# MacroQMK.net
KiCad netlist of a schematic drawn in Altium Designer
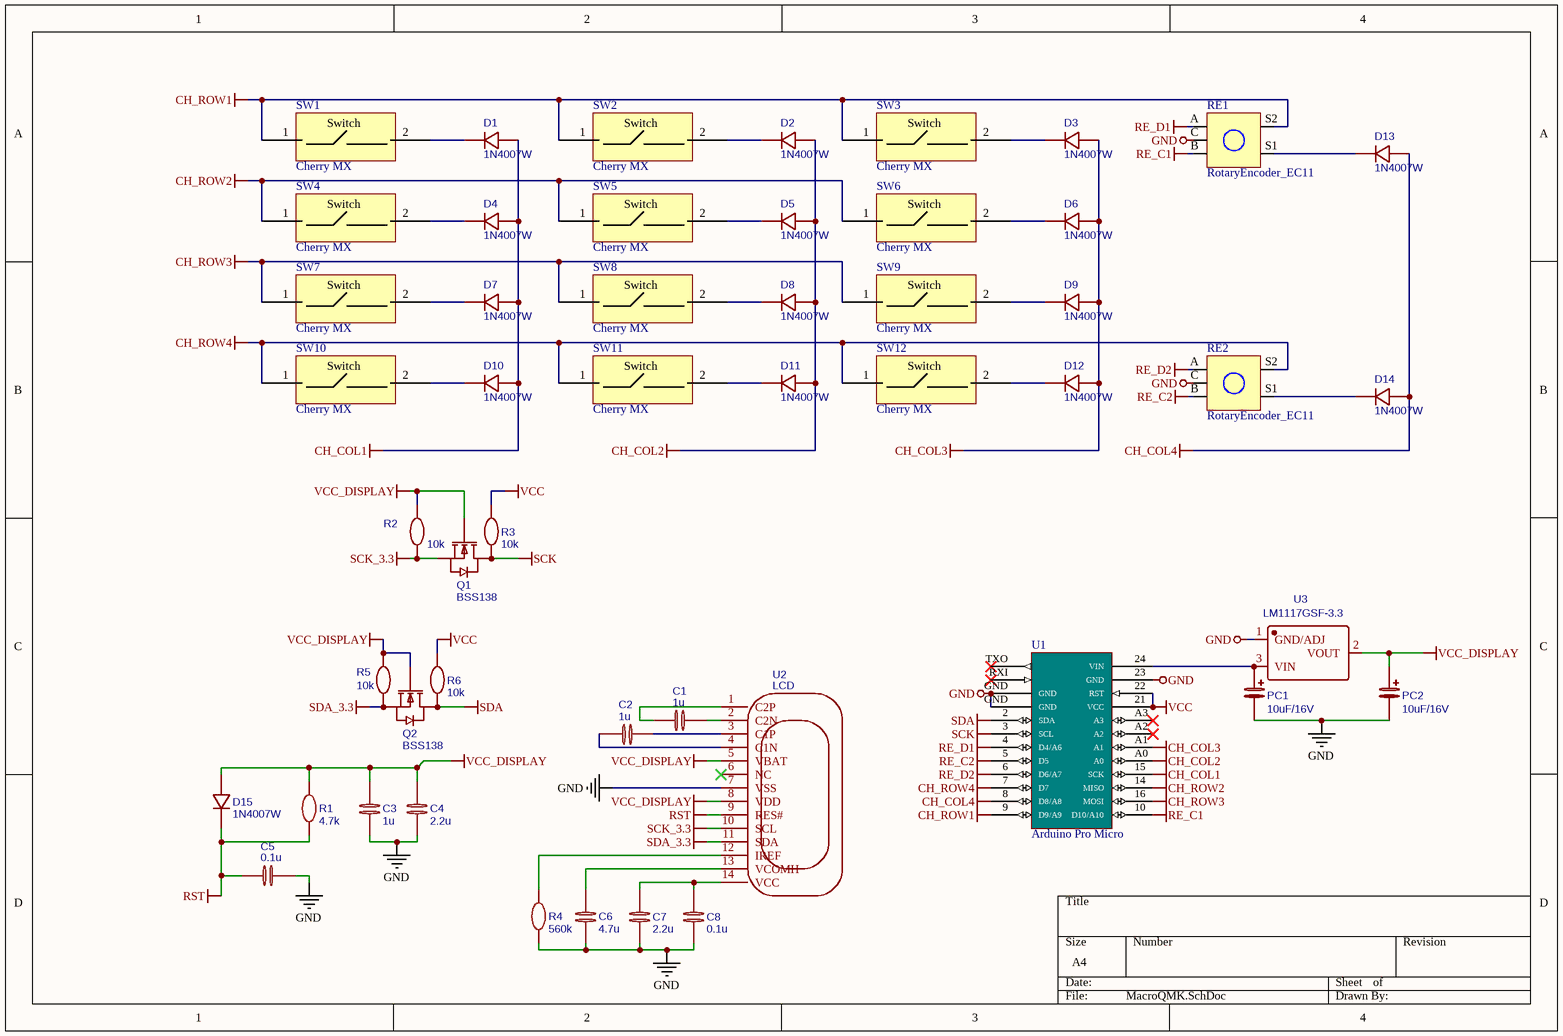
[diagram p0: MacroQMK.SchDoc]

(export (version "E")
  (design (tool "Eeschema 10.0.6"))
  (components
    (comp (ref "C1")
      (value "1u")
      (footprint "C0603")
      (fields (field (name "CONTRIBUTOR") "LCEDA_Lib"))
      (libsource (lib "altium-import") (part "root_0_1u_"))
    )
    (comp (ref "C2")
      (value "1u")
      (footprint "C0603")
      (fields (field (name "CONTRIBUTOR") "LCEDA_Lib"))
      (libsource (lib "altium-import") (part "root_2_1u_"))
    )
    (comp (ref "C3")
      (value "1u")
      (footprint "C0603")
      (fields (field (name "CONTRIBUTOR") "LCEDA_Lib"))
      (libsource (lib "altium-import") (part "root_1_1u_"))
    )
    (comp (ref "C4")
      (value "2.2u")
      (footprint "C0603")
      (fields (field (name "CONTRIBUTOR") "LCEDA_Lib"))
      (libsource (lib "altium-import") (part "root_1_2.2u_"))
    )
    (comp (ref "C5")
      (value "0.1u")
      (footprint "C0603")
      (fields (field (name "CONTRIBUTOR") "LCEDA_Lib"))
      (libsource (lib "altium-import") (part "root_0_0.1u_"))
    )
    (comp (ref "C6")
      (value "4.7u")
      (footprint "C0603")
      (fields (field (name "CONTRIBUTOR") "LCEDA_Lib"))
      (libsource (lib "altium-import") (part "root_1_4.7u_"))
    )
    (comp (ref "C7")
      (value "2.2u")
      (footprint "C0603")
      (fields (field (name "CONTRIBUTOR") "LCEDA_Lib"))
      (libsource (lib "altium-import") (part "root_1_2.2u_"))
    )
    (comp (ref "C8")
      (value "0.1u")
      (footprint "C0603")
      (fields (field (name "CONTRIBUTOR") "LCEDA_Lib"))
      (libsource (lib "altium-import") (part "root_1_0.1u_"))
    )
    (comp (ref "D1")
      (value "1N4007W")
      (footprint "SOD123F")
      (fields (field (name "BOM_SUPPLIER PART") "C328592") (field (name "CONTRIBUTOR") "LCEDA_Lib"))
      (libsource (lib "altium-import") (part "root_2_1N4007W_"))
    )
    (comp (ref "D2")
      (value "1N4007W")
      (footprint "SOD123F")
      (fields (field (name "BOM_SUPPLIER PART") "C328592") (field (name "CONTRIBUTOR") "LCEDA_Lib"))
      (libsource (lib "altium-import") (part "root_2_1N4007W_"))
    )
    (comp (ref "D3")
      (value "1N4007W")
      (footprint "SOD123F")
      (fields (field (name "BOM_SUPPLIER PART") "C328592") (field (name "CONTRIBUTOR") "LCEDA_Lib"))
      (libsource (lib "altium-import") (part "root_2_1N4007W_"))
    )
    (comp (ref "D4")
      (value "1N4007W")
      (footprint "SOD123F")
      (fields (field (name "BOM_SUPPLIER PART") "C328592") (field (name "CONTRIBUTOR") "LCEDA_Lib"))
      (libsource (lib "altium-import") (part "root_2_1N4007W_"))
    )
    (comp (ref "D5")
      (value "1N4007W")
      (footprint "SOD123F")
      (fields (field (name "BOM_SUPPLIER PART") "C328592") (field (name "CONTRIBUTOR") "LCEDA_Lib"))
      (libsource (lib "altium-import") (part "root_2_1N4007W_"))
    )
    (comp (ref "D6")
      (value "1N4007W")
      (footprint "SOD123F")
      (fields (field (name "BOM_SUPPLIER PART") "C328592") (field (name "CONTRIBUTOR") "LCEDA_Lib"))
      (libsource (lib "altium-import") (part "root_2_1N4007W_"))
    )
    (comp (ref "D7")
      (value "1N4007W")
      (footprint "SOD123F")
      (fields (field (name "BOM_SUPPLIER PART") "C328592") (field (name "CONTRIBUTOR") "LCEDA_Lib"))
      (libsource (lib "altium-import") (part "root_2_1N4007W_"))
    )
    (comp (ref "D8")
      (value "1N4007W")
      (footprint "SOD123F")
      (fields (field (name "BOM_SUPPLIER PART") "C328592") (field (name "CONTRIBUTOR") "LCEDA_Lib"))
      (libsource (lib "altium-import") (part "root_2_1N4007W_"))
    )
    (comp (ref "D9")
      (value "1N4007W")
      (footprint "SOD123F")
      (fields (field (name "BOM_SUPPLIER PART") "C328592") (field (name "CONTRIBUTOR") "LCEDA_Lib"))
      (libsource (lib "altium-import") (part "root_2_1N4007W_"))
    )
    (comp (ref "D10")
      (value "1N4007W")
      (footprint "SOD123F")
      (fields (field (name "BOM_SUPPLIER PART") "C328592") (field (name "CONTRIBUTOR") "LCEDA_Lib"))
      (libsource (lib "altium-import") (part "root_2_1N4007W_"))
    )
    (comp (ref "D11")
      (value "1N4007W")
      (footprint "SOD123F")
      (fields (field (name "BOM_SUPPLIER PART") "C328592") (field (name "CONTRIBUTOR") "LCEDA_Lib"))
      (libsource (lib "altium-import") (part "root_2_1N4007W_"))
    )
    (comp (ref "D12")
      (value "1N4007W")
      (footprint "SOD123F")
      (fields (field (name "BOM_SUPPLIER PART") "C328592") (field (name "CONTRIBUTOR") "LCEDA_Lib"))
      (libsource (lib "altium-import") (part "root_2_1N4007W_"))
    )
    (comp (ref "D13")
      (value "1N4007W")
      (footprint "SOD123F")
      (fields (field (name "BOM_SUPPLIER PART") "C328592") (field (name "CONTRIBUTOR") "LCEDA_Lib"))
      (libsource (lib "altium-import") (part "root_2_1N4007W_"))
    )
    (comp (ref "D14")
      (value "1N4007W")
      (footprint "SOD123F")
      (fields (field (name "BOM_SUPPLIER PART") "C328592") (field (name "CONTRIBUTOR") "LCEDA_Lib"))
      (libsource (lib "altium-import") (part "root_2_1N4007W_"))
    )
    (comp (ref "D15")
      (value "1N4007W")
      (footprint "SOD123F")
      (fields (field (name "BOM_SUPPLIER PART") "C328592") (field (name "CONTRIBUTOR") "LCEDA_Lib"))
      (libsource (lib "altium-import") (part "root_3_1N4007W_"))
    )
    (comp (ref "PC1")
      (value "10uF/16V")
      (footprint "CAP POL 1206_3216")
      (fields (field (name "BOM_MANUFACTURER PART") "?"))
      (libsource (lib "altium-import") (part "root_0_10uF/16V_"))
    )
    (comp (ref "PC2")
      (value "10uF/16V")
      (footprint "CAP POL 1206_3216")
      (fields (field (name "BOM_MANUFACTURER PART") "?"))
      (libsource (lib "altium-import") (part "root_0_10uF/16V_"))
    )
    (comp (ref "Q1")
      (value "BSS138")
      (footprint "MICROCHIP SOT-23-3 NB")
      (fields (field (name "BOM_MANUFACTURER PART") "BSS138LT1G") (field (name "BOM_SUPPLIER PART") "C82045"))
      (libsource (lib "altium-import") (part "root_3_BSS138_"))
    )
    (comp (ref "Q2")
      (value "BSS138")
      (footprint "MICROCHIP SOT-23-3 NB")
      (fields (field (name "BOM_MANUFACTURER PART") "BSS138LT1G") (field (name "BOM_SUPPLIER PART") "C82045"))
      (libsource (lib "altium-import") (part "root_3_BSS138_"))
    )
    (comp (ref "R1")
      (value "4.7k")
      (footprint "RES 0402_1005")
      (fields (field (name "CONTRIBUTOR") "LCEDA_Lib"))
      (libsource (lib "altium-import") (part "root_1_4.7k_"))
    )
    (comp (ref "R2")
      (value "10k")
      (footprint "R0603")
      (fields (field (name "CONTRIBUTOR") "LCEDA_Lib"))
      (libsource (lib "altium-import") (part "root_3_10k_"))
    )
    (comp (ref "R3")
      (value "10k")
      (footprint "R0603")
      (fields (field (name "CONTRIBUTOR") "LCEDA_Lib"))
      (libsource (lib "altium-import") (part "root_3_10k_"))
    )
    (comp (ref "R4")
      (value "560k")
      (footprint "R0603")
      (fields (field (name "CONTRIBUTOR") "LCEDA_Lib"))
      (libsource (lib "altium-import") (part "root_1_560k_"))
    )
    (comp (ref "R5")
      (value "10k")
      (footprint "R0603")
      (fields (field (name "CONTRIBUTOR") "LCEDA_Lib"))
      (libsource (lib "altium-import") (part "root_3_10k_"))
    )
    (comp (ref "R6")
      (value "10k")
      (footprint "R0603")
      (fields (field (name "CONTRIBUTOR") "LCEDA_Lib"))
      (libsource (lib "altium-import") (part "root_3_10k_"))
    )
    (comp (ref "RE1")
      (value "RotaryEncoder_EC11")
      (footprint "RotaryEncoder_EC11")
      (libsource (lib "MacroQMK") (part "RotaryEncoder_EC11"))
    )
    (comp (ref "RE2")
      (value "RotaryEncoder_EC11")
      (footprint "RotaryEncoder_EC11")
      (libsource (lib "MacroQMK") (part "RotaryEncoder_EC11"))
    )
    (comp (ref "SW1")
      (value "Cherry MX")
      (footprint "MX_Cherry")
      (libsource (lib "MacroQMK") (part "MX_Cherry"))
    )
    (comp (ref "SW2")
      (value "Cherry MX")
      (footprint "MX_Cherry")
      (libsource (lib "MacroQMK") (part "MX_Cherry"))
    )
    (comp (ref "SW3")
      (value "Cherry MX")
      (footprint "MX_Cherry")
      (libsource (lib "MacroQMK") (part "MX_Cherry"))
    )
    (comp (ref "SW4")
      (value "Cherry MX")
      (footprint "MX_Cherry")
      (libsource (lib "MacroQMK") (part "MX_Cherry"))
    )
    (comp (ref "SW5")
      (value "Cherry MX")
      (footprint "MX_Cherry")
      (libsource (lib "MacroQMK") (part "MX_Cherry"))
    )
    (comp (ref "SW6")
      (value "Cherry MX")
      (footprint "MX_Cherry")
      (libsource (lib "MacroQMK") (part "MX_Cherry"))
    )
    (comp (ref "SW7")
      (value "Cherry MX")
      (footprint "MX_Cherry")
      (libsource (lib "MacroQMK") (part "MX_Cherry"))
    )
    (comp (ref "SW8")
      (value "Cherry MX")
      (footprint "MX_Cherry")
      (libsource (lib "MacroQMK") (part "MX_Cherry"))
    )
    (comp (ref "SW9")
      (value "Cherry MX")
      (footprint "MX_Cherry")
      (libsource (lib "MacroQMK") (part "MX_Cherry"))
    )
    (comp (ref "SW10")
      (value "Cherry MX")
      (footprint "MX_Cherry")
      (libsource (lib "MacroQMK") (part "MX_Cherry"))
    )
    (comp (ref "SW11")
      (value "Cherry MX")
      (footprint "MX_Cherry")
      (libsource (lib "MacroQMK") (part "MX_Cherry"))
    )
    (comp (ref "SW12")
      (value "Cherry MX")
      (footprint "MX_Cherry")
      (libsource (lib "MacroQMK") (part "MX_Cherry"))
    )
    (comp (ref "U1")
      (value "Arduino Pro Micro")
      (footprint "ArduinoProMicro")
      (libsource (lib "MacroQMK") (part "ArduinoProMicro"))
    )
    (comp (ref "U2")
      (value "LCD")
      (footprint "GCT FFC2B28-14")
      (fields (field (name "CONTRIBUTOR") "Jose Manuel Ordo?ez Gongora"))
      (libsource (lib "altium-import") (part "root_3_LCD_"))
    )
    (comp (ref "U3")
      (value "LM1117GSF-3.3")
      (footprint "NEXPERIA SOT-223 BZV90")
      (fields (field (name "BOM_SUPPLIER PART") "C481677") (field (name "CONTRIBUTOR") "LCSC"))
      (libsource (lib "altium-import") (part "root_0_LM1117GSF-3.3_"))
    )
  )
  (nets
    (net (code "1") (name "CH_COL1") (class "Default")
      (node (ref "D1") (pin "2") (pinfunction "2_2") (pintype "passive"))
      (node (ref "D10") (pin "2") (pinfunction "2_2") (pintype "passive"))
      (node (ref "D4") (pin "2") (pinfunction "2_2") (pintype "passive"))
      (node (ref "D7") (pin "2") (pinfunction "2_2") (pintype "passive"))
      (node (ref "U1") (pin "15") (pinfunction "SCK_15") (pintype "bidirectional"))
    )
    (net (code "2") (name "CH_COL2") (class "Default")
      (node (ref "D11") (pin "2") (pinfunction "2_2") (pintype "passive"))
      (node (ref "D2") (pin "2") (pinfunction "2_2") (pintype "passive"))
      (node (ref "D5") (pin "2") (pinfunction "2_2") (pintype "passive"))
      (node (ref "D8") (pin "2") (pinfunction "2_2") (pintype "passive"))
      (node (ref "U1") (pin "A0") (pinfunction "A0_A0") (pintype "bidirectional"))
    )
    (net (code "3") (name "CH_COL3") (class "Default")
      (node (ref "D12") (pin "2") (pinfunction "2_2") (pintype "passive"))
      (node (ref "D3") (pin "2") (pinfunction "2_2") (pintype "passive"))
      (node (ref "D6") (pin "2") (pinfunction "2_2") (pintype "passive"))
      (node (ref "D9") (pin "2") (pinfunction "2_2") (pintype "passive"))
      (node (ref "U1") (pin "A1") (pinfunction "A1_A1") (pintype "bidirectional"))
    )
    (net (code "4") (name "CH_COL4") (class "Default")
      (node (ref "D13") (pin "2") (pinfunction "2_2") (pintype "passive"))
      (node (ref "D14") (pin "2") (pinfunction "2_2") (pintype "passive"))
      (node (ref "U1") (pin "8") (pinfunction "D8/A8_8") (pintype "bidirectional"))
    )
    (net (code "5") (name "CH_ROW1") (class "Default")
      (node (ref "RE1") (pin "S2") (pintype "passive"))
      (node (ref "SW1") (pin "1") (pintype "passive"))
      (node (ref "SW2") (pin "1") (pintype "passive"))
      (node (ref "SW3") (pin "1") (pintype "passive"))
      (node (ref "U1") (pin "9") (pinfunction "D9/A9_9") (pintype "bidirectional"))
    )
    (net (code "6") (name "CH_ROW2") (class "Default")
      (node (ref "SW4") (pin "1") (pintype "passive"))
      (node (ref "SW5") (pin "1") (pintype "passive"))
      (node (ref "SW6") (pin "1") (pintype "passive"))
      (node (ref "U1") (pin "14") (pinfunction "MISO_14") (pintype "bidirectional"))
    )
    (net (code "7") (name "CH_ROW3") (class "Default")
      (node (ref "SW7") (pin "1") (pintype "passive"))
      (node (ref "SW8") (pin "1") (pintype "passive"))
      (node (ref "SW9") (pin "1") (pintype "passive"))
      (node (ref "U1") (pin "16") (pinfunction "MOSI_16") (pintype "bidirectional"))
    )
    (net (code "8") (name "CH_ROW4") (class "Default")
      (node (ref "RE2") (pin "S2") (pintype "passive"))
      (node (ref "SW10") (pin "1") (pintype "passive"))
      (node (ref "SW11") (pin "1") (pintype "passive"))
      (node (ref "SW12") (pin "1") (pintype "passive"))
      (node (ref "U1") (pin "7") (pinfunction "D7_7") (pintype "bidirectional"))
    )
    (net (code "9") (name "GND") (class "Default")
      (node (ref "C3") (pin "1") (pinfunction "1_1") (pintype "passive"))
      (node (ref "C4") (pin "1") (pinfunction "1_1") (pintype "passive"))
      (node (ref "C5") (pin "2") (pinfunction "2_2") (pintype "passive"))
      (node (ref "C6") (pin "1") (pinfunction "1_1") (pintype "passive"))
      (node (ref "C7") (pin "1") (pinfunction "1_1") (pintype "passive"))
      (node (ref "C8") (pin "1") (pinfunction "1_1") (pintype "passive"))
      (node (ref "PC1") (pin "2") (pinfunction "2_2") (pintype "passive"))
      (node (ref "PC2") (pin "2") (pinfunction "2_2") (pintype "passive"))
      (node (ref "R4") (pin "1") (pinfunction "1_1") (pintype "passive"))
      (node (ref "RE1") (pin "C") (pintype "passive"))
      (node (ref "RE2") (pin "C") (pintype "passive"))
      (node (ref "U1") (pin "23") (pinfunction "GND_23") (pintype "power_in"))
      (node (ref "U1") (pin "GND") (pinfunction "GND_GND") (pintype "power_in"))
      (node (ref "U2") (pin "7") (pinfunction "VSS_7") (pintype "passive"))
      (node (ref "U3") (pin "1") (pinfunction "GND/ADJ_1") (pintype "passive"))
    )
    (net (code "10") (name "Net-(D1-Pad1)") (class "Default")
      (node (ref "D1") (pin "1") (pinfunction "1_1") (pintype "passive"))
      (node (ref "SW1") (pin "2") (pintype "passive"))
    )
    (net (code "11") (name "Net-(D2-Pad1)") (class "Default")
      (node (ref "D2") (pin "1") (pinfunction "1_1") (pintype "passive"))
      (node (ref "SW2") (pin "2") (pintype "passive"))
    )
    (net (code "12") (name "Net-(D3-Pad1)") (class "Default")
      (node (ref "D3") (pin "1") (pinfunction "1_1") (pintype "passive"))
      (node (ref "SW3") (pin "2") (pintype "passive"))
    )
    (net (code "13") (name "Net-(D4-Pad1)") (class "Default")
      (node (ref "D4") (pin "1") (pinfunction "1_1") (pintype "passive"))
      (node (ref "SW4") (pin "2") (pintype "passive"))
    )
    (net (code "14") (name "Net-(D5-Pad1)") (class "Default")
      (node (ref "D5") (pin "1") (pinfunction "1_1") (pintype "passive"))
      (node (ref "SW5") (pin "2") (pintype "passive"))
    )
    (net (code "15") (name "Net-(D6-Pad1)") (class "Default")
      (node (ref "D6") (pin "1") (pinfunction "1_1") (pintype "passive"))
      (node (ref "SW6") (pin "2") (pintype "passive"))
    )
    (net (code "16") (name "Net-(D7-Pad1)") (class "Default")
      (node (ref "D7") (pin "1") (pinfunction "1_1") (pintype "passive"))
      (node (ref "SW7") (pin "2") (pintype "passive"))
    )
    (net (code "17") (name "Net-(D8-Pad1)") (class "Default")
      (node (ref "D8") (pin "1") (pinfunction "1_1") (pintype "passive"))
      (node (ref "SW8") (pin "2") (pintype "passive"))
    )
    (net (code "18") (name "Net-(D9-Pad1)") (class "Default")
      (node (ref "D9") (pin "1") (pinfunction "1_1") (pintype "passive"))
      (node (ref "SW9") (pin "2") (pintype "passive"))
    )
    (net (code "19") (name "Net-(D10-Pad1)") (class "Default")
      (node (ref "D10") (pin "1") (pinfunction "1_1") (pintype "passive"))
      (node (ref "SW10") (pin "2") (pintype "passive"))
    )
    (net (code "20") (name "Net-(D11-Pad1)") (class "Default")
      (node (ref "D11") (pin "1") (pinfunction "1_1") (pintype "passive"))
      (node (ref "SW11") (pin "2") (pintype "passive"))
    )
    (net (code "21") (name "Net-(D12-Pad1)") (class "Default")
      (node (ref "D12") (pin "1") (pinfunction "1_1") (pintype "passive"))
      (node (ref "SW12") (pin "2") (pintype "passive"))
    )
    (net (code "22") (name "Net-(D13-Pad1)") (class "Default")
      (node (ref "D13") (pin "1") (pinfunction "1_1") (pintype "passive"))
      (node (ref "RE1") (pin "S1") (pintype "passive"))
    )
    (net (code "23") (name "Net-(D14-Pad1)") (class "Default")
      (node (ref "D14") (pin "1") (pinfunction "1_1") (pintype "passive"))
      (node (ref "RE2") (pin "S1") (pintype "passive"))
    )
    (net (code "24") (name "Net-(U1-VIN)") (class "Default")
      (node (ref "PC1") (pin "1") (pinfunction "1_1") (pintype "passive"))
      (node (ref "U1") (pin "24") (pinfunction "VIN_24") (pintype "power_in"))
      (node (ref "U3") (pin "3") (pinfunction "VIN_3") (pintype "passive"))
    )
    (net (code "25") (name "Net-(U2-C1N)") (class "Default")
      (node (ref "C2") (pin "2") (pinfunction "2_2") (pintype "passive"))
      (node (ref "U2") (pin "4") (pinfunction "C1N_4") (pintype "passive"))
    )
    (net (code "26") (name "Net-(U2-C1P)") (class "Default")
      (node (ref "C2") (pin "1") (pinfunction "1_1") (pintype "passive"))
      (node (ref "U2") (pin "3") (pinfunction "C1P_3") (pintype "passive"))
    )
    (net (code "27") (name "Net-(U2-C2N)") (class "Default")
      (node (ref "C1") (pin "2") (pinfunction "2_2") (pintype "passive"))
      (node (ref "U2") (pin "2") (pinfunction "C2N_2") (pintype "passive"))
    )
    (net (code "28") (name "Net-(U2-C2P)") (class "Default")
      (node (ref "C1") (pin "1") (pinfunction "1_1") (pintype "passive"))
      (node (ref "U2") (pin "1") (pinfunction "C2P_1") (pintype "passive"))
    )
    (net (code "29") (name "Net-(U2-IREF)") (class "Default")
      (node (ref "R4") (pin "2") (pinfunction "2_2") (pintype "passive"))
      (node (ref "U2") (pin "12") (pinfunction "IREF_12") (pintype "passive"))
    )
    (net (code "30") (name "Net-(U2-VCC)") (class "Default")
      (node (ref "C7") (pin "2") (pinfunction "2_2") (pintype "passive"))
      (node (ref "C8") (pin "2") (pinfunction "2_2") (pintype "passive"))
      (node (ref "U2") (pin "14") (pinfunction "VCC_14") (pintype "passive"))
    )
    (net (code "31") (name "Net-(U2-VCOMH)") (class "Default")
      (node (ref "C6") (pin "2") (pinfunction "2_2") (pintype "passive"))
      (node (ref "U2") (pin "13") (pinfunction "VCOMH_13") (pintype "passive"))
    )
    (net (code "32") (name "RE_C1") (class "Default")
      (node (ref "RE1") (pin "B") (pintype "passive"))
      (node (ref "U1") (pin "10") (pinfunction "D10/A10_10") (pintype "bidirectional"))
    )
    (net (code "33") (name "RE_C2") (class "Default")
      (node (ref "RE2") (pin "B") (pintype "passive"))
      (node (ref "U1") (pin "5") (pinfunction "D5_5") (pintype "bidirectional"))
    )
    (net (code "34") (name "RE_D1") (class "Default")
      (node (ref "RE1") (pin "A") (pintype "passive"))
      (node (ref "U1") (pin "4") (pinfunction "D4/A6_4") (pintype "bidirectional"))
    )
    (net (code "35") (name "RE_D2") (class "Default")
      (node (ref "RE2") (pin "A") (pintype "passive"))
      (node (ref "U1") (pin "6") (pinfunction "D6/A7_6") (pintype "bidirectional"))
    )
    (net (code "36") (name "RST") (class "Default")
      (node (ref "C5") (pin "1") (pinfunction "1_1") (pintype "passive"))
      (node (ref "D15") (pin "1") (pinfunction "1_1") (pintype "passive"))
      (node (ref "R1") (pin "1") (pinfunction "1_1") (pintype "passive"))
      (node (ref "U2") (pin "9") (pinfunction "RES#_9") (pintype "passive"))
    )
    (net (code "37") (name "SCK") (class "Default")
      (node (ref "Q1") (pin "3") (pinfunction "D_3") (pintype "passive"))
      (node (ref "R3") (pin "2") (pinfunction "2_2") (pintype "passive"))
      (node (ref "U1") (pin "3") (pinfunction "SCL_3") (pintype "bidirectional"))
    )
    (net (code "38") (name "SCK_3.3") (class "Default")
      (node (ref "Q1") (pin "2") (pinfunction "S_2") (pintype "passive"))
      (node (ref "R2") (pin "2") (pinfunction "2_2") (pintype "passive"))
      (node (ref "U2") (pin "10") (pinfunction "SCL_10") (pintype "passive"))
    )
    (net (code "39") (name "SDA") (class "Default")
      (node (ref "Q2") (pin "3") (pinfunction "D_3") (pintype "passive"))
      (node (ref "R6") (pin "2") (pinfunction "2_2") (pintype "passive"))
      (node (ref "U1") (pin "2") (pinfunction "SDA_2") (pintype "bidirectional"))
    )
    (net (code "40") (name "SDA_3.3") (class "Default")
      (node (ref "Q2") (pin "2") (pinfunction "S_2") (pintype "passive"))
      (node (ref "R5") (pin "2") (pinfunction "2_2") (pintype "passive"))
      (node (ref "U2") (pin "11") (pinfunction "SDA_11") (pintype "passive"))
    )
    (net (code "41") (name "VCC") (class "Default")
      (node (ref "R3") (pin "1") (pinfunction "1_1") (pintype "passive"))
      (node (ref "R6") (pin "1") (pinfunction "1_1") (pintype "passive"))
      (node (ref "U1") (pin "21") (pinfunction "VCC_21") (pintype "power_in"))
      (node (ref "U1") (pin "22") (pinfunction "RST_22") (pintype "input"))
    )
    (net (code "42") (name "VCC_DISPLAY") (class "Default")
      (node (ref "C3") (pin "2") (pinfunction "2_2") (pintype "passive"))
      (node (ref "C4") (pin "2") (pinfunction "2_2") (pintype "passive"))
      (node (ref "D15") (pin "2") (pinfunction "2_2") (pintype "passive"))
      (node (ref "PC2") (pin "1") (pinfunction "1_1") (pintype "passive"))
      (node (ref "Q1") (pin "1") (pinfunction "G_1") (pintype "passive"))
      (node (ref "Q2") (pin "1") (pinfunction "G_1") (pintype "passive"))
      (node (ref "R1") (pin "2") (pinfunction "2_2") (pintype "passive"))
      (node (ref "R2") (pin "1") (pinfunction "1_1") (pintype "passive"))
      (node (ref "R5") (pin "1") (pinfunction "1_1") (pintype "passive"))
      (node (ref "U2") (pin "5") (pinfunction "VBAT_5") (pintype "passive"))
      (node (ref "U2") (pin "8") (pinfunction "VDD_8") (pintype "passive"))
      (node (ref "U3") (pin "2") (pinfunction "VOUT_2") (pintype "passive"))
    )
    (net (code "43") (name "unconnected-(U1-PadA2)") (class "Default")
      (node (ref "U1") (pin "A2") (pinfunction "A2_A2") (pintype "bidirectional+no_connect"))
    )
    (net (code "44") (name "unconnected-(U1-PadA3)") (class "Default")
      (node (ref "U1") (pin "A3") (pinfunction "A3_A3") (pintype "bidirectional+no_connect"))
    )
    (net (code "45") (name "unconnected-(U1-PadRXI)") (class "Default")
      (node (ref "U1") (pin "RXI") (pintype "input+no_connect"))
    )
    (net (code "46") (name "unconnected-(U1-PadTXO)") (class "Default")
      (node (ref "U1") (pin "TXO") (pintype "output+no_connect"))
    )
    (net (code "47") (name "unconnected-(U2-NC-Pad6)") (class "Default")
      (node (ref "U2") (pin "6") (pinfunction "NC_6") (pintype "passive+no_connect"))
    )
  )
)
